# SSM4.net
KiCad netlist of a schematic drawn in EAGLE
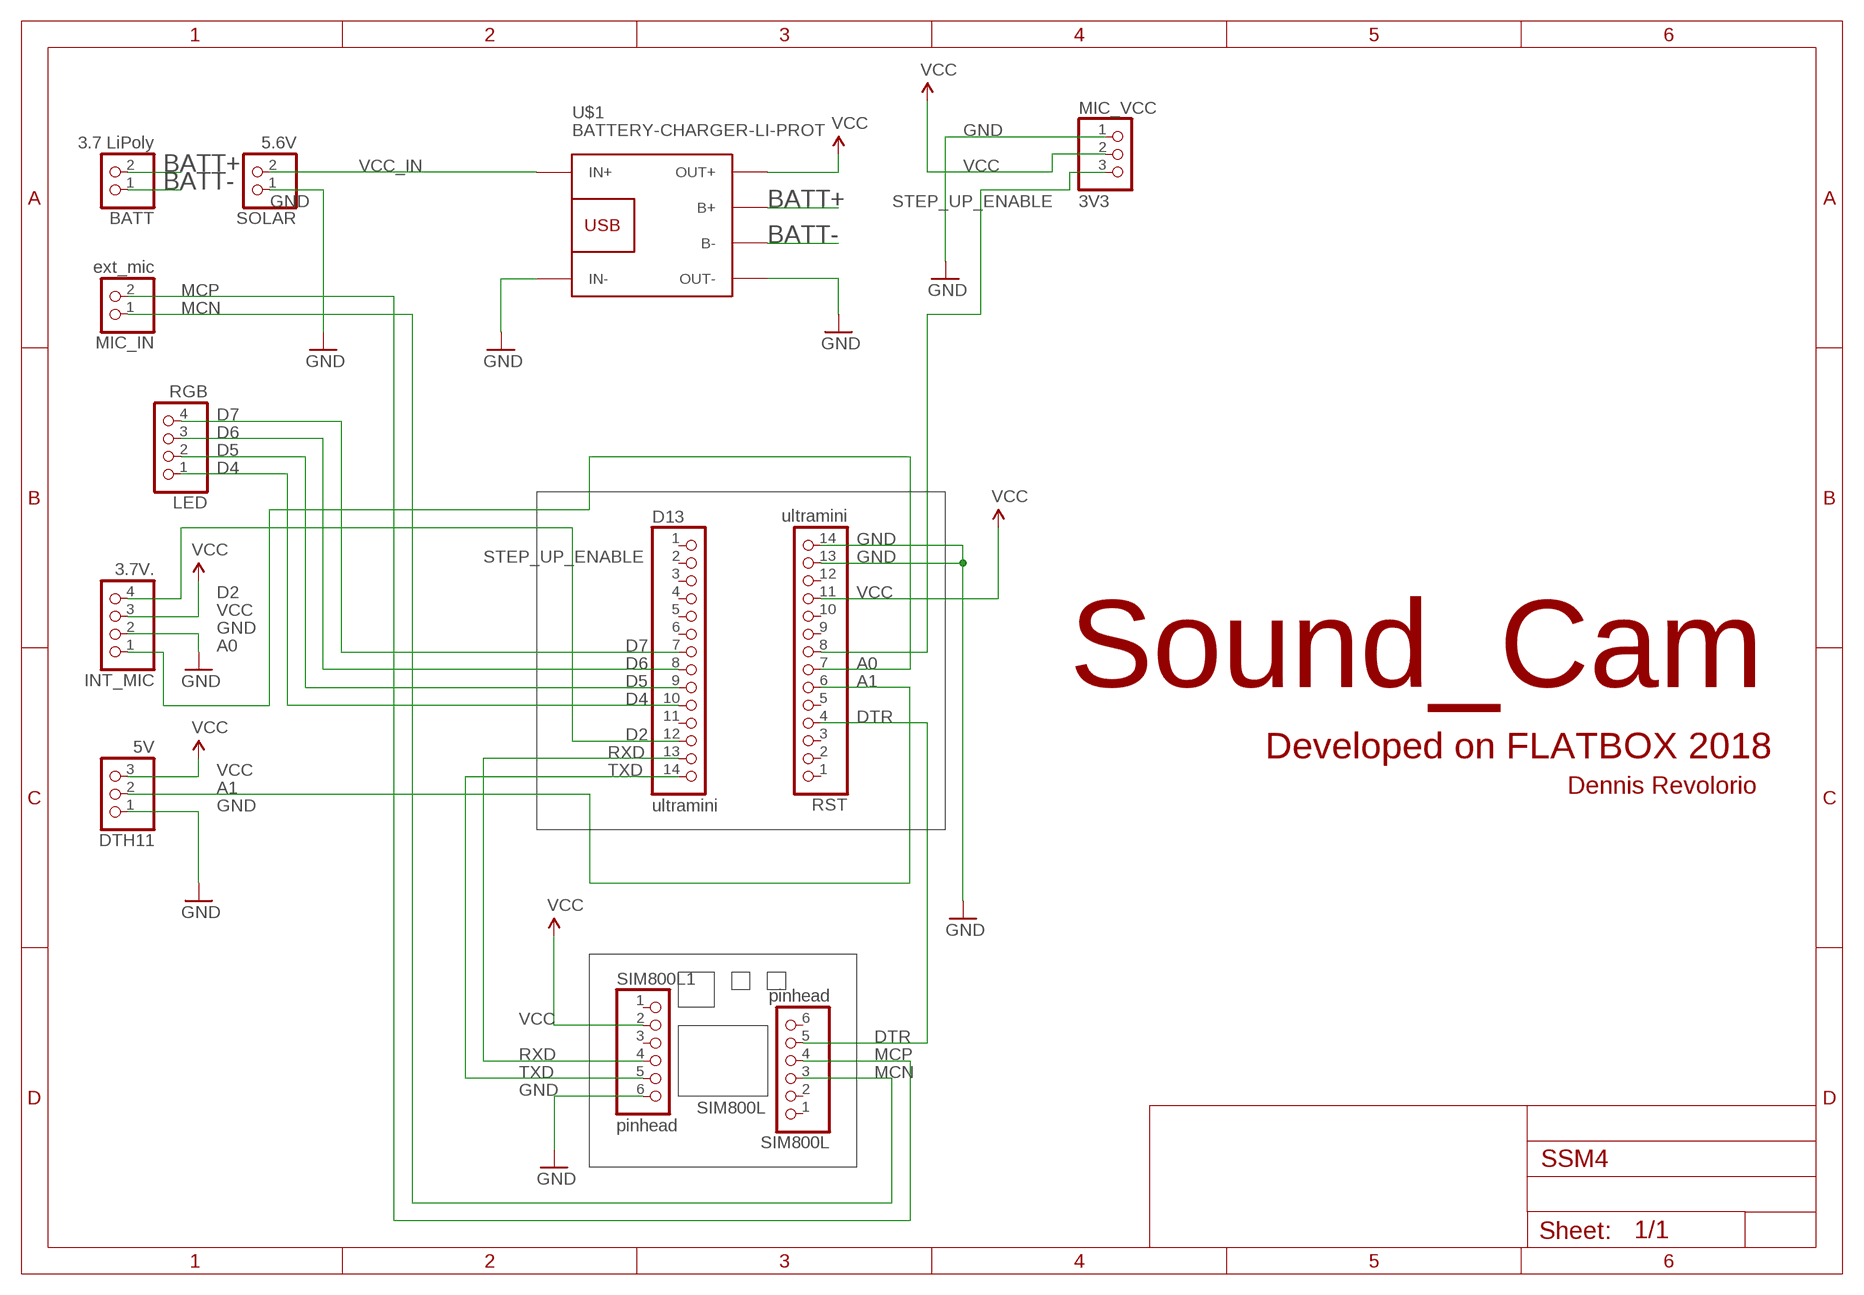
[diagram p0: schematic, sheet 1]

(export (version "E")
  (design (tool "Eeschema 10.0.6"))
  (components
    (comp (ref "BATT")
      (value "3.7 LiPoly")
      (footprint "eagle-import:1X02")
      (libsource (lib "eagle-import") (part "PINHD-1X2"))
    )
    (comp (ref "D13")
      (value "ultramini")
      (footprint "eagle-import:1X14")
      (libsource (lib "eagle-import") (part "PINHD-1X14"))
    )
    (comp (ref "DTH11")
      (value "5V")
      (footprint "eagle-import:1X03")
      (libsource (lib "eagle-import") (part "PINHD-1X3"))
    )
    (comp (ref "INT_MIC")
      (value "3.7V.")
      (footprint "eagle-import:1X04")
      (libsource (lib "eagle-import") (part "PINHD-1X4"))
    )
    (comp (ref "LED")
      (value "RGB")
      (footprint "eagle-import:1X04")
      (libsource (lib "eagle-import") (part "PINHD-1X4"))
    )
    (comp (ref "MIC_IN")
      (value "ext_mic")
      (footprint "eagle-import:1X02")
      (libsource (lib "eagle-import") (part "PINHD-1X2"))
    )
    (comp (ref "MIC_VCC")
      (value "3V3")
      (footprint "eagle-import:1X03")
      (libsource (lib "eagle-import") (part "pinhead_325_PINHD-1X3"))
    )
    (comp (ref "RST")
      (value "ultramini")
      (footprint "eagle-import:1X14")
      (libsource (lib "eagle-import") (part "PINHD-1X14"))
    )
    (comp (ref "SIM800L")
      (value "pinhead")
      (footprint "eagle-import:1X06")
      (libsource (lib "eagle-import") (part "PINHD-1X6"))
    )
    (comp (ref "SIM800L1")
      (value "pinhead")
      (footprint "eagle-import:1X06")
      (libsource (lib "eagle-import") (part "PINHD-1X6"))
    )
    (comp (ref "SOLAR")
      (value "5.6V")
      (footprint "eagle-import:1X02")
      (libsource (lib "eagle-import") (part "PINHD-1X2"))
    )
    (comp (ref "U$1")
      (value "BATTERY-CHARGER-LI-PROT")
      (footprint "eagle-import:BATTERY-CHARGER-LI-PROT")
      (libsource (lib "eagle-import") (part "BATTERY-CHARGER-LI-PROT"))
    )
  )
  (nets
    (net (code "1") (name "/A0") (class "Default")
      (node (ref "INT_MIC") (pin "1") (pinfunction "1_1") (pintype "passive"))
      (node (ref "RST") (pin "7") (pinfunction "7_7") (pintype "passive"))
    )
    (net (code "2") (name "/A1") (class "Default")
      (node (ref "DTH11") (pin "2") (pinfunction "2_2") (pintype "passive"))
      (node (ref "RST") (pin "6") (pinfunction "6_6") (pintype "passive"))
    )
    (net (code "3") (name "/BATT+") (class "Default")
      (node (ref "BATT") (pin "2") (pinfunction "2_2") (pintype "passive"))
      (node (ref "U$1") (pin "B+") (pinfunction "B+_B+") (pintype "bidirectional"))
    )
    (net (code "4") (name "/BATT-") (class "Default")
      (node (ref "BATT") (pin "1") (pinfunction "1_1") (pintype "passive"))
      (node (ref "U$1") (pin "B-") (pinfunction "B-_B-") (pintype "bidirectional"))
    )
    (net (code "5") (name "/D2") (class "Default")
      (node (ref "D13") (pin "12") (pinfunction "12_12") (pintype "passive"))
      (node (ref "INT_MIC") (pin "4") (pinfunction "4_4") (pintype "passive"))
    )
    (net (code "6") (name "/D4") (class "Default")
      (node (ref "D13") (pin "10") (pinfunction "10_10") (pintype "passive"))
      (node (ref "LED") (pin "1") (pinfunction "1_1") (pintype "passive"))
    )
    (net (code "7") (name "/D5") (class "Default")
      (node (ref "D13") (pin "9") (pinfunction "9_9") (pintype "passive"))
      (node (ref "LED") (pin "2") (pinfunction "2_2") (pintype "passive"))
    )
    (net (code "8") (name "/D6") (class "Default")
      (node (ref "D13") (pin "8") (pinfunction "8_8") (pintype "passive"))
      (node (ref "LED") (pin "3") (pinfunction "3_3") (pintype "passive"))
    )
    (net (code "9") (name "/D7") (class "Default")
      (node (ref "D13") (pin "7") (pinfunction "7_7") (pintype "passive"))
      (node (ref "LED") (pin "4") (pinfunction "4_4") (pintype "passive"))
    )
    (net (code "10") (name "/DTR") (class "Default")
      (node (ref "RST") (pin "4") (pinfunction "4_4") (pintype "passive"))
      (node (ref "SIM800L") (pin "5") (pinfunction "5_5") (pintype "passive"))
    )
    (net (code "11") (name "/MCN") (class "Default")
      (node (ref "MIC_IN") (pin "1") (pinfunction "1_1") (pintype "passive"))
      (node (ref "SIM800L") (pin "3") (pinfunction "3_3") (pintype "passive"))
    )
    (net (code "12") (name "/MCP") (class "Default")
      (node (ref "MIC_IN") (pin "2") (pinfunction "2_2") (pintype "passive"))
      (node (ref "SIM800L") (pin "4") (pinfunction "4_4") (pintype "passive"))
    )
    (net (code "13") (name "/RXD") (class "Default")
      (node (ref "D13") (pin "13") (pinfunction "13_13") (pintype "passive"))
      (node (ref "SIM800L1") (pin "4") (pinfunction "4_4") (pintype "passive"))
    )
    (net (code "14") (name "/STEP_UP_ENABLE") (class "Default")
      (node (ref "MIC_VCC") (pin "3") (pinfunction "3_3") (pintype "passive"))
      (node (ref "RST") (pin "8") (pinfunction "8_8") (pintype "passive"))
    )
    (net (code "15") (name "/TXD") (class "Default")
      (node (ref "D13") (pin "14") (pinfunction "14_14") (pintype "passive"))
      (node (ref "SIM800L1") (pin "5") (pinfunction "5_5") (pintype "passive"))
    )
    (net (code "16") (name "/VCC_IN") (class "Default")
      (node (ref "SOLAR") (pin "2") (pinfunction "2_2") (pintype "passive"))
      (node (ref "U$1") (pin "IN+") (pinfunction "IN+_IN+") (pintype "bidirectional"))
    )
    (net (code "17") (name "GND") (class "Default")
      (node (ref "DTH11") (pin "1") (pinfunction "1_1") (pintype "passive"))
      (node (ref "INT_MIC") (pin "2") (pinfunction "2_2") (pintype "passive"))
      (node (ref "MIC_VCC") (pin "1") (pinfunction "1_1") (pintype "passive"))
      (node (ref "RST") (pin "13") (pinfunction "13_13") (pintype "passive"))
      (node (ref "RST") (pin "14") (pinfunction "14_14") (pintype "passive"))
      (node (ref "SIM800L1") (pin "6") (pinfunction "6_6") (pintype "passive"))
      (node (ref "SOLAR") (pin "1") (pinfunction "1_1") (pintype "passive"))
      (node (ref "U$1") (pin "IN-") (pinfunction "IN-_IN-") (pintype "bidirectional"))
      (node (ref "U$1") (pin "OUT-") (pinfunction "OUT-_OUT-") (pintype "bidirectional"))
    )
    (net (code "18") (name "VCC") (class "Default")
      (node (ref "DTH11") (pin "3") (pinfunction "3_3") (pintype "passive"))
      (node (ref "INT_MIC") (pin "3") (pinfunction "3_3") (pintype "passive"))
      (node (ref "MIC_VCC") (pin "2") (pinfunction "2_2") (pintype "passive"))
      (node (ref "RST") (pin "11") (pinfunction "11_11") (pintype "passive"))
      (node (ref "SIM800L1") (pin "2") (pinfunction "2_2") (pintype "passive"))
      (node (ref "U$1") (pin "OUT+") (pinfunction "OUT+_OUT+") (pintype "bidirectional"))
    )
    (net (code "19") (name "unconnected-(D13-Pad1)") (class "Default")
      (node (ref "D13") (pin "1") (pinfunction "1_1") (pintype "passive"))
    )
    (net (code "20") (name "unconnected-(D13-Pad2)") (class "Default")
      (node (ref "D13") (pin "2") (pinfunction "2_2") (pintype "passive"))
    )
    (net (code "21") (name "unconnected-(D13-Pad3)") (class "Default")
      (node (ref "D13") (pin "3") (pinfunction "3_3") (pintype "passive"))
    )
    (net (code "22") (name "unconnected-(D13-Pad4)") (class "Default")
      (node (ref "D13") (pin "4") (pinfunction "4_4") (pintype "passive"))
    )
    (net (code "23") (name "unconnected-(D13-Pad5)") (class "Default")
      (node (ref "D13") (pin "5") (pinfunction "5_5") (pintype "passive"))
    )
    (net (code "24") (name "unconnected-(D13-Pad6)") (class "Default")
      (node (ref "D13") (pin "6") (pinfunction "6_6") (pintype "passive"))
    )
    (net (code "25") (name "unconnected-(D13-Pad11)") (class "Default")
      (node (ref "D13") (pin "11") (pinfunction "11_11") (pintype "passive"))
    )
    (net (code "26") (name "unconnected-(RST-Pad1)") (class "Default")
      (node (ref "RST") (pin "1") (pinfunction "1_1") (pintype "passive"))
    )
    (net (code "27") (name "unconnected-(RST-Pad2)") (class "Default")
      (node (ref "RST") (pin "2") (pinfunction "2_2") (pintype "passive"))
    )
    (net (code "28") (name "unconnected-(RST-Pad3)") (class "Default")
      (node (ref "RST") (pin "3") (pinfunction "3_3") (pintype "passive"))
    )
    (net (code "29") (name "unconnected-(RST-Pad5)") (class "Default")
      (node (ref "RST") (pin "5") (pinfunction "5_5") (pintype "passive"))
    )
    (net (code "30") (name "unconnected-(RST-Pad9)") (class "Default")
      (node (ref "RST") (pin "9") (pinfunction "9_9") (pintype "passive"))
    )
    (net (code "31") (name "unconnected-(RST-Pad10)") (class "Default")
      (node (ref "RST") (pin "10") (pinfunction "10_10") (pintype "passive"))
    )
    (net (code "32") (name "unconnected-(RST-Pad12)") (class "Default")
      (node (ref "RST") (pin "12") (pinfunction "12_12") (pintype "passive"))
    )
    (net (code "33") (name "unconnected-(SIM800L-Pad1)") (class "Default")
      (node (ref "SIM800L") (pin "1") (pinfunction "1_1") (pintype "passive"))
    )
    (net (code "34") (name "unconnected-(SIM800L-Pad2)") (class "Default")
      (node (ref "SIM800L") (pin "2") (pinfunction "2_2") (pintype "passive"))
    )
    (net (code "35") (name "unconnected-(SIM800L-Pad6)") (class "Default")
      (node (ref "SIM800L") (pin "6") (pinfunction "6_6") (pintype "passive"))
    )
    (net (code "36") (name "unconnected-(SIM800L1-Pad1)") (class "Default")
      (node (ref "SIM800L1") (pin "1") (pinfunction "1_1") (pintype "passive"))
    )
    (net (code "37") (name "unconnected-(SIM800L1-Pad3)") (class "Default")
      (node (ref "SIM800L1") (pin "3") (pinfunction "3_3") (pintype "passive"))
    )
  )
)
